# SmallTime-v02.net
KiCad netlist of a schematic drawn in EAGLE
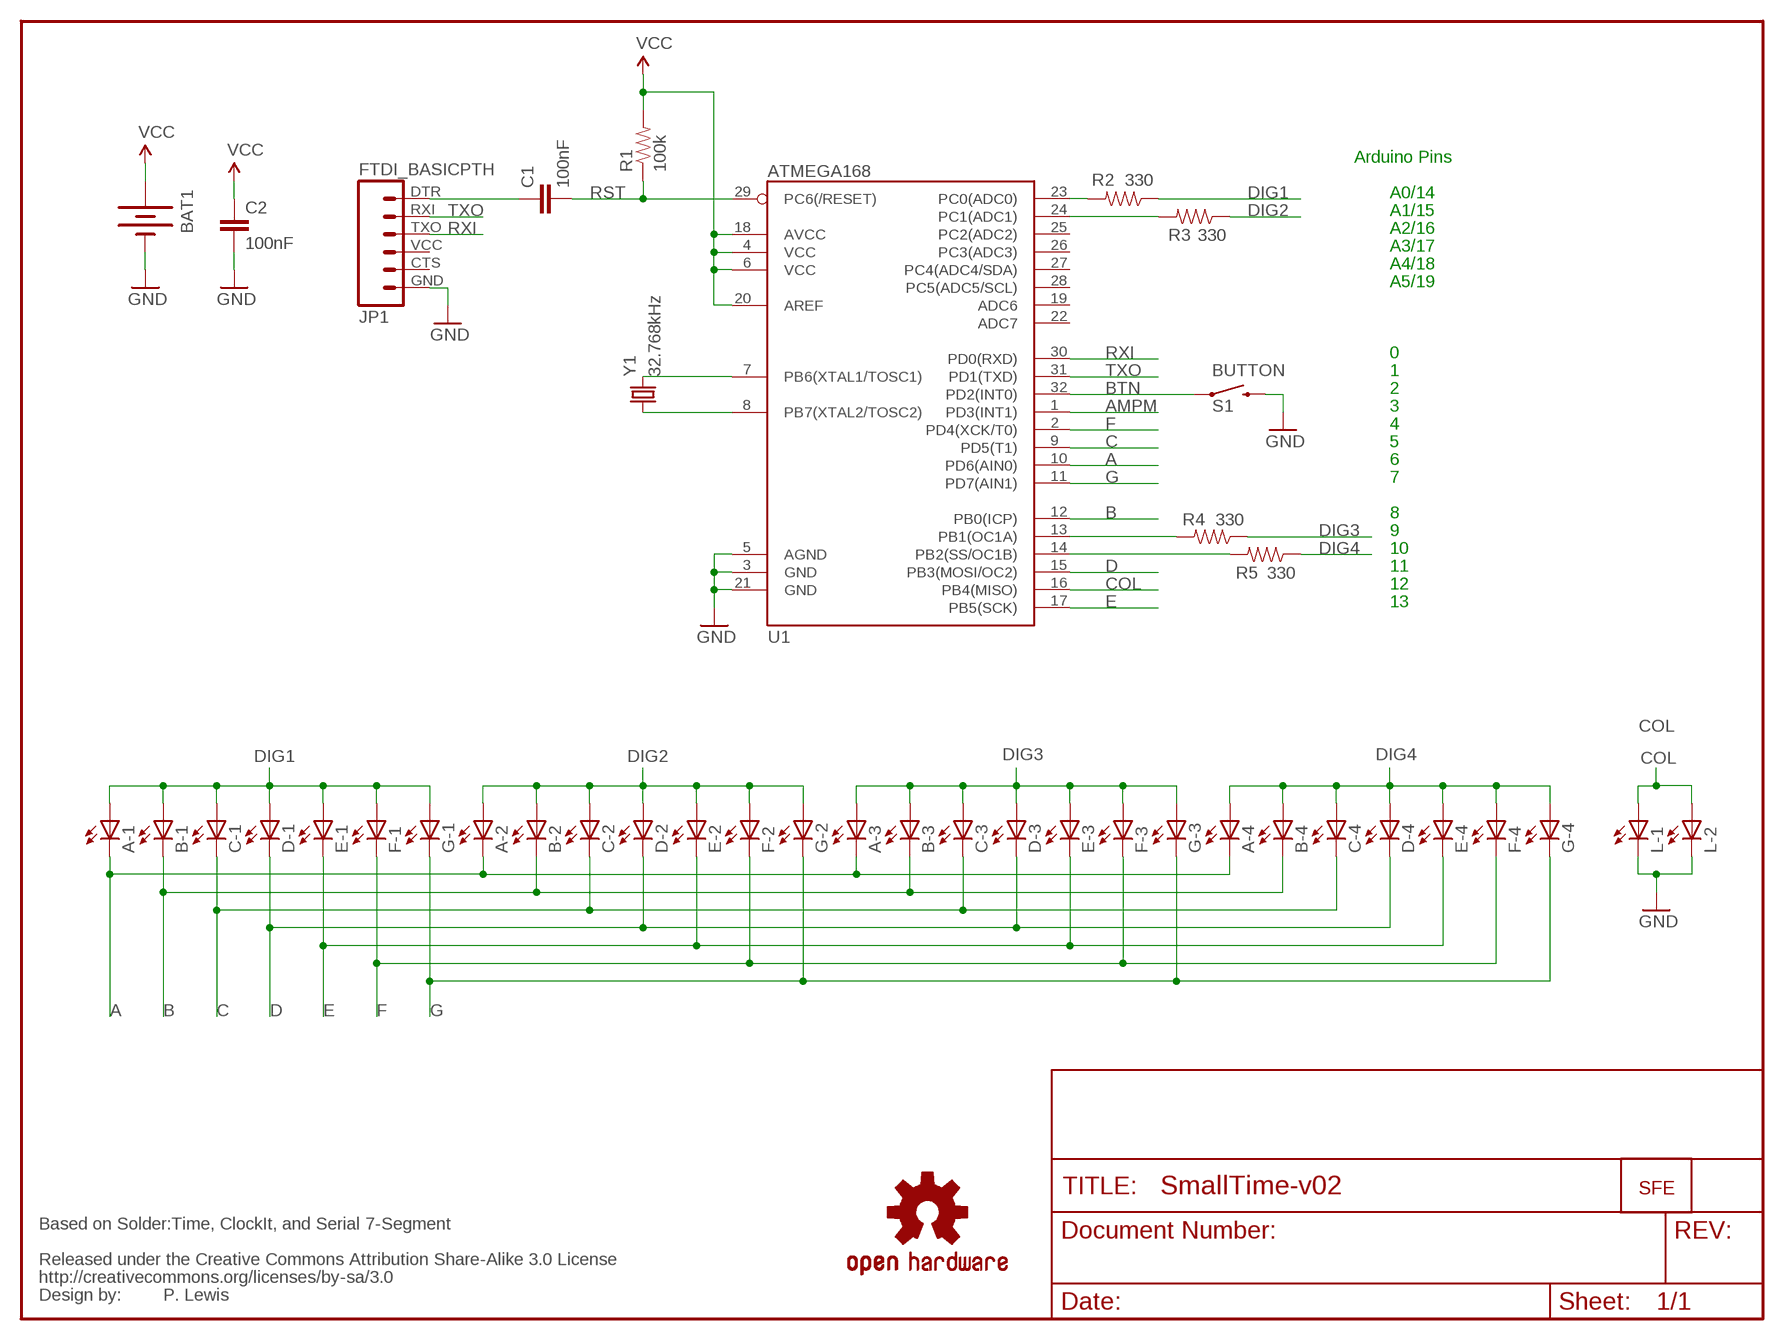
[diagram p0: schematic, sheet 1]

(export (version "E")
  (design (tool "Eeschema 10.0.6"))
  (components
    (comp (ref "A-1")
      (value "LEDBOTTOM")
      (footprint "eagle-import:LED-1206-BOTTOM-TINGHT")
      (libsource (lib "eagle-import") (part "LEDBOTTOM"))
    )
    (comp (ref "A-2")
      (value "LEDBOTTOM")
      (footprint "eagle-import:LED-1206-BOTTOM-TINGHT")
      (libsource (lib "eagle-import") (part "LEDBOTTOM"))
    )
    (comp (ref "A-3")
      (value "LEDBOTTOM")
      (footprint "eagle-import:LED-1206-BOTTOM-TINGHT")
      (libsource (lib "eagle-import") (part "LEDBOTTOM"))
    )
    (comp (ref "A-4")
      (value "LEDBOTTOM")
      (footprint "eagle-import:LED-1206-BOTTOM-TINGHT")
      (libsource (lib "eagle-import") (part "LEDBOTTOM"))
    )
    (comp (ref "B-1")
      (value "LEDBOTTOM")
      (footprint "eagle-import:LED-1206-BOTTOM-TINGHT")
      (libsource (lib "eagle-import") (part "LEDBOTTOM"))
    )
    (comp (ref "B-2")
      (value "LEDBOTTOM")
      (footprint "eagle-import:LED-1206-BOTTOM-TINGHT")
      (libsource (lib "eagle-import") (part "LEDBOTTOM"))
    )
    (comp (ref "B-3")
      (value "LEDBOTTOM")
      (footprint "eagle-import:LED-1206-BOTTOM-TINGHT")
      (libsource (lib "eagle-import") (part "LEDBOTTOM"))
    )
    (comp (ref "B-4")
      (value "LEDBOTTOM")
      (footprint "eagle-import:LED-1206-BOTTOM-TINGHT")
      (libsource (lib "eagle-import") (part "LEDBOTTOM"))
    )
    (comp (ref "BAT1")
      (value "BATTERYFOB")
      (footprint "eagle-import:BATTERY_20MM_PTH_COMPACT")
      (libsource (lib "eagle-import") (part "BATTERYFOB"))
    )
    (comp (ref "C-1")
      (value "LEDBOTTOM")
      (footprint "eagle-import:LED-1206-BOTTOM-TINGHT")
      (libsource (lib "eagle-import") (part "LEDBOTTOM"))
    )
    (comp (ref "C-2")
      (value "LEDBOTTOM")
      (footprint "eagle-import:LED-1206-BOTTOM-TINGHT")
      (libsource (lib "eagle-import") (part "LEDBOTTOM"))
    )
    (comp (ref "C-3")
      (value "LEDBOTTOM")
      (footprint "eagle-import:LED-1206-BOTTOM-TINGHT")
      (libsource (lib "eagle-import") (part "LEDBOTTOM"))
    )
    (comp (ref "C-4")
      (value "LEDBOTTOM")
      (footprint "eagle-import:LED-1206-BOTTOM-TINGHT")
      (libsource (lib "eagle-import") (part "LEDBOTTOM"))
    )
    (comp (ref "C1")
      (value "100nF")
      (footprint "eagle-import:0603-CAP")
      (libsource (lib "eagle-import") (part "CAP0603-CAP"))
    )
    (comp (ref "C2")
      (value "100nF")
      (footprint "eagle-import:0603-CAP")
      (libsource (lib "eagle-import") (part "CAP0603-CAP"))
    )
    (comp (ref "D-1")
      (value "LEDBOTTOM")
      (footprint "eagle-import:LED-1206-BOTTOM-TINGHT")
      (libsource (lib "eagle-import") (part "LEDBOTTOM"))
    )
    (comp (ref "D-2")
      (value "LEDBOTTOM")
      (footprint "eagle-import:LED-1206-BOTTOM-TINGHT")
      (libsource (lib "eagle-import") (part "LEDBOTTOM"))
    )
    (comp (ref "D-3")
      (value "LEDBOTTOM")
      (footprint "eagle-import:LED-1206-BOTTOM-TINGHT")
      (libsource (lib "eagle-import") (part "LEDBOTTOM"))
    )
    (comp (ref "D-4")
      (value "LEDBOTTOM")
      (footprint "eagle-import:LED-1206-BOTTOM-TINGHT")
      (libsource (lib "eagle-import") (part "LEDBOTTOM"))
    )
    (comp (ref "E-1")
      (value "LEDBOTTOM")
      (footprint "eagle-import:LED-1206-BOTTOM-TINGHT")
      (libsource (lib "eagle-import") (part "LEDBOTTOM"))
    )
    (comp (ref "E-2")
      (value "LEDBOTTOM")
      (footprint "eagle-import:LED-1206-BOTTOM-TINGHT")
      (libsource (lib "eagle-import") (part "LEDBOTTOM"))
    )
    (comp (ref "E-3")
      (value "LEDBOTTOM")
      (footprint "eagle-import:LED-1206-BOTTOM-TINGHT")
      (libsource (lib "eagle-import") (part "LEDBOTTOM"))
    )
    (comp (ref "E-4")
      (value "LEDBOTTOM")
      (footprint "eagle-import:LED-1206-BOTTOM-TINGHT")
      (libsource (lib "eagle-import") (part "LEDBOTTOM"))
    )
    (comp (ref "F-1")
      (value "LEDBOTTOM")
      (footprint "eagle-import:LED-1206-BOTTOM-TINGHT")
      (libsource (lib "eagle-import") (part "LEDBOTTOM"))
    )
    (comp (ref "F-2")
      (value "LEDBOTTOM")
      (footprint "eagle-import:LED-1206-BOTTOM-TINGHT")
      (libsource (lib "eagle-import") (part "LEDBOTTOM"))
    )
    (comp (ref "F-3")
      (value "LEDBOTTOM")
      (footprint "eagle-import:LED-1206-BOTTOM-TINGHT")
      (libsource (lib "eagle-import") (part "LEDBOTTOM"))
    )
    (comp (ref "F-4")
      (value "LEDBOTTOM")
      (footprint "eagle-import:LED-1206-BOTTOM-TINGHT")
      (libsource (lib "eagle-import") (part "LEDBOTTOM"))
    )
    (comp (ref "G-1")
      (value "LEDBOTTOM")
      (footprint "eagle-import:LED-1206-BOTTOM-TINGHT")
      (libsource (lib "eagle-import") (part "LEDBOTTOM"))
    )
    (comp (ref "G-2")
      (value "LEDBOTTOM")
      (footprint "eagle-import:LED-1206-BOTTOM-TINGHT")
      (libsource (lib "eagle-import") (part "LEDBOTTOM"))
    )
    (comp (ref "G-3")
      (value "LEDBOTTOM")
      (footprint "eagle-import:LED-1206-BOTTOM-TINGHT")
      (libsource (lib "eagle-import") (part "LEDBOTTOM"))
    )
    (comp (ref "G-4")
      (value "LEDBOTTOM")
      (footprint "eagle-import:LED-1206-BOTTOM-TINGHT")
      (libsource (lib "eagle-import") (part "LEDBOTTOM"))
    )
    (comp (ref "JP1")
      (value "FTDI_BASICPTH")
      (footprint "eagle-import:FTDI_BASIC")
      (libsource (lib "eagle-import") (part "FTDI_BASICPTH"))
    )
    (comp (ref "L-1")
      (value "LEDBOTTOM")
      (footprint "eagle-import:LED-1206-BOTTOM-TINGHT")
      (libsource (lib "eagle-import") (part "LEDBOTTOM"))
    )
    (comp (ref "L-2")
      (value "LEDBOTTOM")
      (footprint "eagle-import:LED-1206-BOTTOM-TINGHT")
      (libsource (lib "eagle-import") (part "LEDBOTTOM"))
    )
    (comp (ref "R1")
      (value "100k")
      (footprint "eagle-import:0603-RES")
      (libsource (lib "eagle-import") (part "RESISTOR0603-RES"))
    )
    (comp (ref "R2")
      (value "330")
      (footprint "eagle-import:0603-RES")
      (libsource (lib "eagle-import") (part "RESISTOR0603-RES"))
    )
    (comp (ref "R3")
      (value "330")
      (footprint "eagle-import:0603-RES")
      (libsource (lib "eagle-import") (part "RESISTOR0603-RES"))
    )
    (comp (ref "R4")
      (value "330")
      (footprint "eagle-import:0603-RES")
      (libsource (lib "eagle-import") (part "RESISTOR0603-RES"))
    )
    (comp (ref "R5")
      (value "330")
      (footprint "eagle-import:0603-RES")
      (libsource (lib "eagle-import") (part "RESISTOR0603-RES"))
    )
    (comp (ref "S1")
      (value "BUTTON")
      (footprint "eagle-import:TACTILE-PTH-SIDEEZ")
      (libsource (lib "eagle-import") (part "SWITCH-MOMENTARY-2SIDE_EZ"))
    )
    (comp (ref "U$2")
      (value "CREATIVE_COMMONS")
      (footprint "eagle-import:CREATIVE_COMMONS")
      (libsource (lib "eagle-import") (part "CREATIVE_COMMONS"))
    )
    (comp (ref "U$4")
      (value "OSHW-LOGOS")
      (footprint "eagle-import:OSHW-LOGO-S")
      (libsource (lib "eagle-import") (part "OSHW-LOGOS"))
    )
    (comp (ref "U$5")
      (value "LOGO-SFENW2")
      (footprint "eagle-import:SFE-NEW-WEB")
      (libsource (lib "eagle-import") (part "LOGO-SFENW2"))
    )
    (comp (ref "U1")
      (value "ATMEGA168")
      (footprint "eagle-import:TQFP32-08")
      (libsource (lib "eagle-import") (part "ATMEGA168"))
    )
    (comp (ref "Y1")
      (value "32.768kHz")
      (footprint "eagle-import:TC26HEZ")
      (libsource (lib "eagle-import") (part "CRYSTALTC26H_EZ"))
    )
  )
  (nets
    (net (code "1") (name "/A") (class "Default")
      (node (ref "A-1") (pin "C") (pinfunction "C_C") (pintype "passive"))
      (node (ref "A-2") (pin "C") (pinfunction "C_C") (pintype "passive"))
      (node (ref "A-3") (pin "C") (pinfunction "C_C") (pintype "passive"))
      (node (ref "A-4") (pin "C") (pinfunction "C_C") (pintype "passive"))
      (node (ref "U1") (pin "10") (pinfunction "PD6(AIN0)_10") (pintype "bidirectional"))
    )
    (net (code "2") (name "/AMPM") (class "Default")
      (node (ref "U1") (pin "1") (pinfunction "PD3(INT1)_1") (pintype "bidirectional"))
    )
    (net (code "3") (name "/B") (class "Default")
      (node (ref "B-1") (pin "C") (pinfunction "C_C") (pintype "passive"))
      (node (ref "B-2") (pin "C") (pinfunction "C_C") (pintype "passive"))
      (node (ref "B-3") (pin "C") (pinfunction "C_C") (pintype "passive"))
      (node (ref "B-4") (pin "C") (pinfunction "C_C") (pintype "passive"))
      (node (ref "U1") (pin "12") (pinfunction "PB0(ICP)_12") (pintype "bidirectional"))
    )
    (net (code "4") (name "/BTN") (class "Default")
      (node (ref "S1") (pin "1") (pinfunction "1_1") (pintype "passive"))
      (node (ref "U1") (pin "32") (pinfunction "PD2(INT0)_32") (pintype "bidirectional"))
    )
    (net (code "5") (name "/C") (class "Default")
      (node (ref "C-1") (pin "C") (pinfunction "C_C") (pintype "passive"))
      (node (ref "C-2") (pin "C") (pinfunction "C_C") (pintype "passive"))
      (node (ref "C-3") (pin "C") (pinfunction "C_C") (pintype "passive"))
      (node (ref "C-4") (pin "C") (pinfunction "C_C") (pintype "passive"))
      (node (ref "U1") (pin "9") (pinfunction "PD5(T1)_9") (pintype "bidirectional"))
    )
    (net (code "6") (name "/COL") (class "Default")
      (node (ref "L-1") (pin "A") (pinfunction "A_A") (pintype "passive"))
      (node (ref "L-2") (pin "A") (pinfunction "A_A") (pintype "passive"))
      (node (ref "U1") (pin "16") (pinfunction "PB4(MISO)_16") (pintype "bidirectional"))
    )
    (net (code "7") (name "/D") (class "Default")
      (node (ref "D-1") (pin "C") (pinfunction "C_C") (pintype "passive"))
      (node (ref "D-2") (pin "C") (pinfunction "C_C") (pintype "passive"))
      (node (ref "D-3") (pin "C") (pinfunction "C_C") (pintype "passive"))
      (node (ref "D-4") (pin "C") (pinfunction "C_C") (pintype "passive"))
      (node (ref "U1") (pin "15") (pinfunction "PB3(MOSI/OC2)_15") (pintype "bidirectional"))
    )
    (net (code "8") (name "/DIG1") (class "Default")
      (node (ref "A-1") (pin "A") (pinfunction "A_A") (pintype "passive"))
      (node (ref "B-1") (pin "A") (pinfunction "A_A") (pintype "passive"))
      (node (ref "C-1") (pin "A") (pinfunction "A_A") (pintype "passive"))
      (node (ref "D-1") (pin "A") (pinfunction "A_A") (pintype "passive"))
      (node (ref "E-1") (pin "A") (pinfunction "A_A") (pintype "passive"))
      (node (ref "F-1") (pin "A") (pinfunction "A_A") (pintype "passive"))
      (node (ref "G-1") (pin "A") (pinfunction "A_A") (pintype "passive"))
      (node (ref "R2") (pin "1") (pinfunction "1_1") (pintype "passive"))
    )
    (net (code "9") (name "/DIG2") (class "Default")
      (node (ref "A-2") (pin "A") (pinfunction "A_A") (pintype "passive"))
      (node (ref "B-2") (pin "A") (pinfunction "A_A") (pintype "passive"))
      (node (ref "C-2") (pin "A") (pinfunction "A_A") (pintype "passive"))
      (node (ref "D-2") (pin "A") (pinfunction "A_A") (pintype "passive"))
      (node (ref "E-2") (pin "A") (pinfunction "A_A") (pintype "passive"))
      (node (ref "F-2") (pin "A") (pinfunction "A_A") (pintype "passive"))
      (node (ref "G-2") (pin "A") (pinfunction "A_A") (pintype "passive"))
      (node (ref "R3") (pin "1") (pinfunction "1_1") (pintype "passive"))
    )
    (net (code "10") (name "/DIG3") (class "Default")
      (node (ref "A-3") (pin "A") (pinfunction "A_A") (pintype "passive"))
      (node (ref "B-3") (pin "A") (pinfunction "A_A") (pintype "passive"))
      (node (ref "C-3") (pin "A") (pinfunction "A_A") (pintype "passive"))
      (node (ref "D-3") (pin "A") (pinfunction "A_A") (pintype "passive"))
      (node (ref "E-3") (pin "A") (pinfunction "A_A") (pintype "passive"))
      (node (ref "F-3") (pin "A") (pinfunction "A_A") (pintype "passive"))
      (node (ref "G-3") (pin "A") (pinfunction "A_A") (pintype "passive"))
      (node (ref "R4") (pin "1") (pinfunction "1_1") (pintype "passive"))
    )
    (net (code "11") (name "/DIG4") (class "Default")
      (node (ref "A-4") (pin "A") (pinfunction "A_A") (pintype "passive"))
      (node (ref "B-4") (pin "A") (pinfunction "A_A") (pintype "passive"))
      (node (ref "C-4") (pin "A") (pinfunction "A_A") (pintype "passive"))
      (node (ref "D-4") (pin "A") (pinfunction "A_A") (pintype "passive"))
      (node (ref "E-4") (pin "A") (pinfunction "A_A") (pintype "passive"))
      (node (ref "F-4") (pin "A") (pinfunction "A_A") (pintype "passive"))
      (node (ref "G-4") (pin "A") (pinfunction "A_A") (pintype "passive"))
      (node (ref "R5") (pin "1") (pinfunction "1_1") (pintype "passive"))
    )
    (net (code "12") (name "/E") (class "Default")
      (node (ref "E-1") (pin "C") (pinfunction "C_C") (pintype "passive"))
      (node (ref "E-2") (pin "C") (pinfunction "C_C") (pintype "passive"))
      (node (ref "E-3") (pin "C") (pinfunction "C_C") (pintype "passive"))
      (node (ref "E-4") (pin "C") (pinfunction "C_C") (pintype "passive"))
      (node (ref "U1") (pin "17") (pinfunction "PB5(SCK)_17") (pintype "bidirectional"))
    )
    (net (code "13") (name "/F") (class "Default")
      (node (ref "F-1") (pin "C") (pinfunction "C_C") (pintype "passive"))
      (node (ref "F-2") (pin "C") (pinfunction "C_C") (pintype "passive"))
      (node (ref "F-3") (pin "C") (pinfunction "C_C") (pintype "passive"))
      (node (ref "F-4") (pin "C") (pinfunction "C_C") (pintype "passive"))
      (node (ref "U1") (pin "2") (pinfunction "PD4(XCK/T0)_2") (pintype "bidirectional"))
    )
    (net (code "14") (name "/G") (class "Default")
      (node (ref "G-1") (pin "C") (pinfunction "C_C") (pintype "passive"))
      (node (ref "G-2") (pin "C") (pinfunction "C_C") (pintype "passive"))
      (node (ref "G-3") (pin "C") (pinfunction "C_C") (pintype "passive"))
      (node (ref "G-4") (pin "C") (pinfunction "C_C") (pintype "passive"))
      (node (ref "U1") (pin "11") (pinfunction "PD7(AIN1)_11") (pintype "bidirectional"))
    )
    (net (code "15") (name "/RST") (class "Default")
      (node (ref "C1") (pin "2") (pinfunction "2_2") (pintype "passive"))
      (node (ref "R1") (pin "1") (pinfunction "1_1") (pintype "passive"))
      (node (ref "U1") (pin "29") (pinfunction "PC6(/RESET)_29") (pintype "bidirectional"))
    )
    (net (code "16") (name "/RXI") (class "Default")
      (node (ref "JP1") (pin "TXO") (pinfunction "3_TXO") (pintype "passive"))
      (node (ref "U1") (pin "30") (pinfunction "PD0(RXD)_30") (pintype "bidirectional"))
    )
    (net (code "17") (name "/TXO") (class "Default")
      (node (ref "JP1") (pin "RXI") (pinfunction "2_RXI") (pintype "passive"))
      (node (ref "U1") (pin "31") (pinfunction "PD1(TXD)_31") (pintype "bidirectional"))
    )
    (net (code "18") (name "GND") (class "Default")
      (node (ref "BAT1") (pin "2") (pinfunction "-_2") (pintype "power_in"))
      (node (ref "C2") (pin "2") (pinfunction "2_2") (pintype "passive"))
      (node (ref "JP1") (pin "GND") (pinfunction "6_GND") (pintype "passive"))
      (node (ref "L-1") (pin "C") (pinfunction "C_C") (pintype "passive"))
      (node (ref "L-2") (pin "C") (pinfunction "C_C") (pintype "passive"))
      (node (ref "S1") (pin "2") (pinfunction "2_2") (pintype "passive"))
      (node (ref "U1") (pin "21") (pinfunction "GND_21") (pintype "bidirectional"))
      (node (ref "U1") (pin "3") (pinfunction "GND_3") (pintype "bidirectional"))
      (node (ref "U1") (pin "5") (pinfunction "AGND_5") (pintype "bidirectional"))
    )
    (net (code "19") (name "Net-(JP1-1)") (class "Default")
      (node (ref "C1") (pin "1") (pinfunction "1_1") (pintype "passive"))
      (node (ref "JP1") (pin "DTR") (pinfunction "1_DTR") (pintype "passive"))
    )
    (net (code "20") (name "Net-(U1-PB1(OC1A))") (class "Default")
      (node (ref "R4") (pin "2") (pinfunction "2_2") (pintype "passive"))
      (node (ref "U1") (pin "13") (pinfunction "PB1(OC1A)_13") (pintype "bidirectional"))
    )
    (net (code "21") (name "Net-(U1-PB2(SS{slash}OC1B))") (class "Default")
      (node (ref "R5") (pin "2") (pinfunction "2_2") (pintype "passive"))
      (node (ref "U1") (pin "14") (pinfunction "PB2(SS/OC1B)_14") (pintype "bidirectional"))
    )
    (net (code "22") (name "Net-(U1-PB6(XTAL1{slash}TOSC1))") (class "Default")
      (node (ref "U1") (pin "7") (pinfunction "PB6(XTAL1/TOSC1)_7") (pintype "bidirectional"))
      (node (ref "Y1") (pin "2") (pinfunction "2_2") (pintype "passive"))
    )
    (net (code "23") (name "Net-(U1-PB7(XTAL2{slash}TOSC2))") (class "Default")
      (node (ref "U1") (pin "8") (pinfunction "PB7(XTAL2/TOSC2)_8") (pintype "bidirectional"))
      (node (ref "Y1") (pin "1") (pinfunction "1_1") (pintype "passive"))
    )
    (net (code "24") (name "Net-(U1-PC0(ADC0))") (class "Default")
      (node (ref "R2") (pin "2") (pinfunction "2_2") (pintype "passive"))
      (node (ref "U1") (pin "23") (pinfunction "PC0(ADC0)_23") (pintype "bidirectional"))
    )
    (net (code "25") (name "Net-(U1-PC1(ADC1))") (class "Default")
      (node (ref "R3") (pin "2") (pinfunction "2_2") (pintype "passive"))
      (node (ref "U1") (pin "24") (pinfunction "PC1(ADC1)_24") (pintype "bidirectional"))
    )
    (net (code "26") (name "VCC") (class "Default")
      (node (ref "BAT1") (pin "1") (pinfunction "+_1") (pintype "power_in"))
      (node (ref "C2") (pin "1") (pinfunction "1_1") (pintype "passive"))
      (node (ref "R1") (pin "2") (pinfunction "2_2") (pintype "passive"))
      (node (ref "U1") (pin "18") (pinfunction "AVCC_18") (pintype "bidirectional"))
      (node (ref "U1") (pin "20") (pinfunction "AREF_20") (pintype "bidirectional"))
      (node (ref "U1") (pin "4") (pinfunction "VCC_4") (pintype "bidirectional"))
      (node (ref "U1") (pin "6") (pinfunction "VCC_6") (pintype "bidirectional"))
    )
    (net (code "27") (name "unconnected-(JP1-4-PadVCC)") (class "Default")
      (node (ref "JP1") (pin "VCC") (pinfunction "4_VCC") (pintype "passive"))
    )
    (net (code "28") (name "unconnected-(JP1-5-PadCTS)") (class "Default")
      (node (ref "JP1") (pin "CTS") (pinfunction "5_CTS") (pintype "passive"))
    )
    (net (code "29") (name "unconnected-(U1-ADC6-Pad19)") (class "Default")
      (node (ref "U1") (pin "19") (pinfunction "ADC6_19") (pintype "bidirectional"))
    )
    (net (code "30") (name "unconnected-(U1-ADC7-Pad22)") (class "Default")
      (node (ref "U1") (pin "22") (pinfunction "ADC7_22") (pintype "bidirectional"))
    )
    (net (code "31") (name "unconnected-(U1-PC2(ADC2)-Pad25)") (class "Default")
      (node (ref "U1") (pin "25") (pinfunction "PC2(ADC2)_25") (pintype "bidirectional"))
    )
    (net (code "32") (name "unconnected-(U1-PC3(ADC3)-Pad26)") (class "Default")
      (node (ref "U1") (pin "26") (pinfunction "PC3(ADC3)_26") (pintype "bidirectional"))
    )
    (net (code "33") (name "unconnected-(U1-PC4(ADC4{slash}SDA)-Pad27)") (class "Default")
      (node (ref "U1") (pin "27") (pinfunction "PC4(ADC4/SDA)_27") (pintype "bidirectional"))
    )
    (net (code "34") (name "unconnected-(U1-PC5(ADC5{slash}SCL)-Pad28)") (class "Default")
      (node (ref "U1") (pin "28") (pinfunction "PC5(ADC5/SCL)_28") (pintype "bidirectional"))
    )
  )
)
